# MCU176.net
KiCad netlist of a schematic drawn in Altium Designer
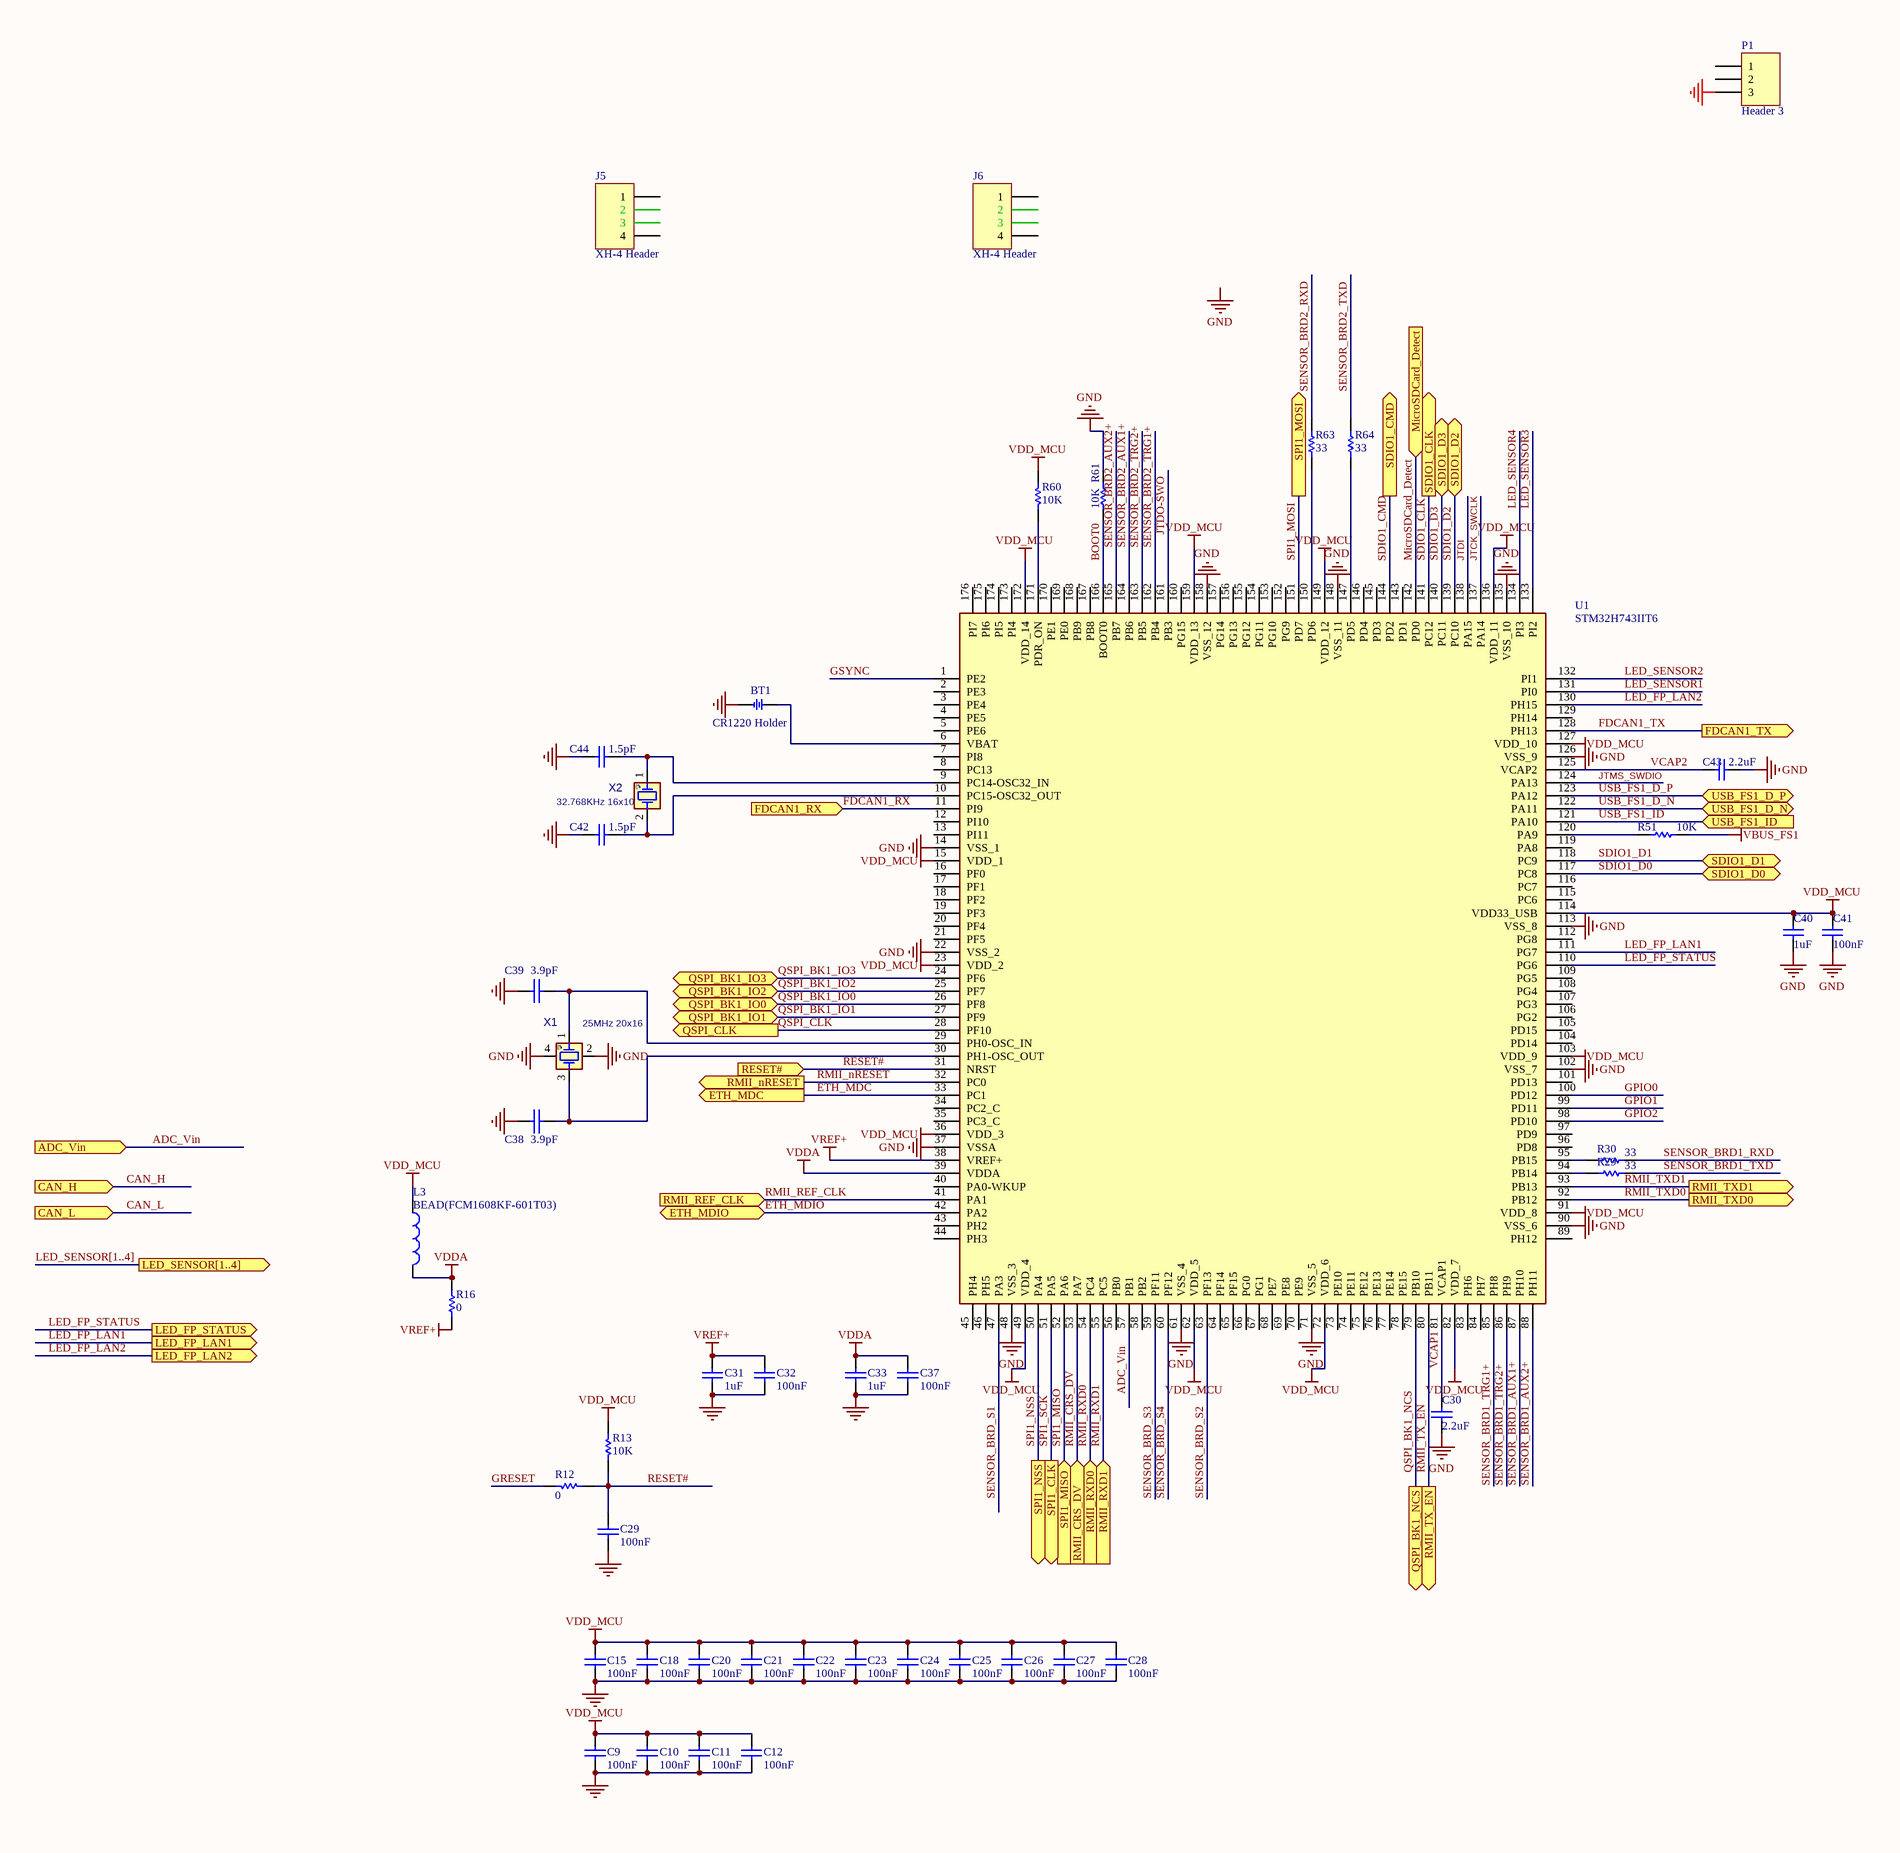
[diagram p0: MCU176.SchDoc, left]
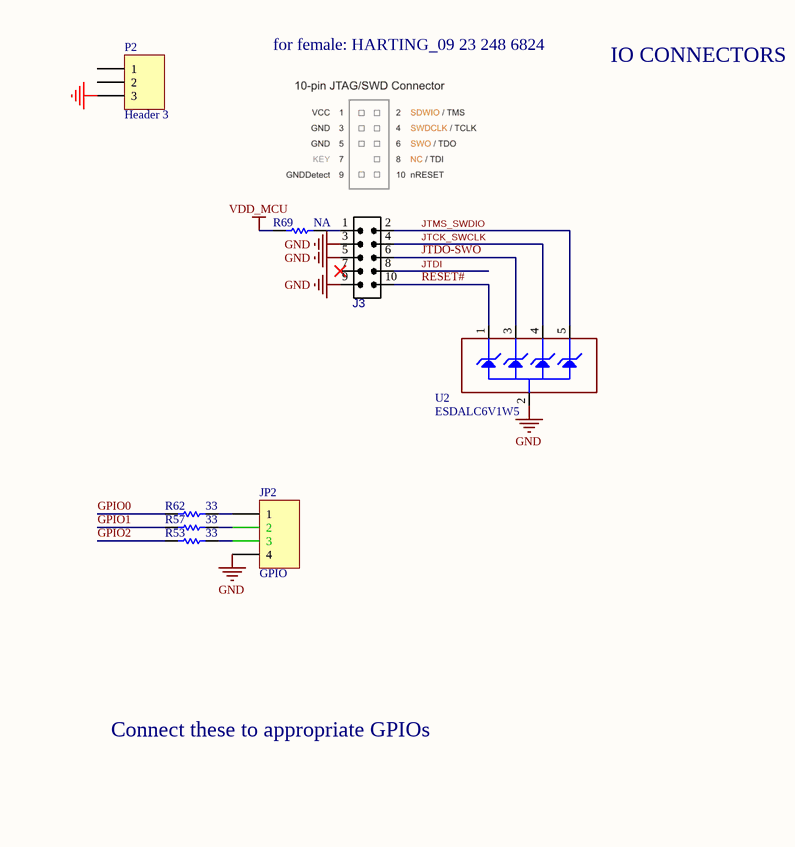
[diagram p1: MCU176.SchDoc, right]

(export (version "E")
  (design (tool "Eeschema 10.0.6"))
  (components
    (comp (ref "BT1")
      (value "CR1220 Holder")
      (footprint "BTH1220")
      (description "BATTERY HOLDER, CR1220")
      (libsource (lib "battery") (part "BATH_CR1220"))
    )
    (comp (ref "C9")
      (value "100nF")
      (footprint "C0603")
      (fields (field (name "PUBLISHER") "Altium Limited"))
      (libsource (lib "Miscellaneous Devices") (part "CAP"))
    )
    (comp (ref "C10")
      (value "100nF")
      (footprint "C0603")
      (fields (field (name "PUBLISHER") "Altium Limited"))
      (libsource (lib "Miscellaneous Devices") (part "CAP"))
    )
    (comp (ref "C11")
      (value "100nF")
      (footprint "C0603")
      (fields (field (name "PUBLISHER") "Altium Limited"))
      (libsource (lib "Miscellaneous Devices") (part "CAP"))
    )
    (comp (ref "C12")
      (value "100nF")
      (footprint "C0603")
      (fields (field (name "PUBLISHER") "Altium Limited"))
      (libsource (lib "Miscellaneous Devices") (part "CAP"))
    )
    (comp (ref "C15")
      (value "100nF")
      (footprint "C0603")
      (fields (field (name "PUBLISHER") "Altium Limited"))
      (libsource (lib "Miscellaneous Devices") (part "CAP"))
    )
    (comp (ref "C18")
      (value "100nF")
      (footprint "C0603")
      (fields (field (name "PUBLISHER") "Altium Limited"))
      (libsource (lib "Miscellaneous Devices") (part "CAP"))
    )
    (comp (ref "C20")
      (value "100nF")
      (footprint "C0603")
      (fields (field (name "PUBLISHER") "Altium Limited"))
      (libsource (lib "Miscellaneous Devices") (part "CAP"))
    )
    (comp (ref "C21")
      (value "100nF")
      (footprint "C0603")
      (fields (field (name "PUBLISHER") "Altium Limited"))
      (libsource (lib "Miscellaneous Devices") (part "CAP"))
    )
    (comp (ref "C22")
      (value "100nF")
      (footprint "C0603")
      (fields (field (name "PUBLISHER") "Altium Limited"))
      (libsource (lib "Miscellaneous Devices") (part "CAP"))
    )
    (comp (ref "C23")
      (value "100nF")
      (footprint "C0603")
      (fields (field (name "PUBLISHER") "Altium Limited"))
      (libsource (lib "Miscellaneous Devices") (part "CAP"))
    )
    (comp (ref "C24")
      (value "100nF")
      (footprint "C0603")
      (fields (field (name "PUBLISHER") "Altium Limited"))
      (libsource (lib "Miscellaneous Devices") (part "CAP"))
    )
    (comp (ref "C25")
      (value "100nF")
      (footprint "C0603")
      (fields (field (name "PUBLISHER") "Altium Limited"))
      (libsource (lib "Miscellaneous Devices") (part "CAP"))
    )
    (comp (ref "C26")
      (value "100nF")
      (footprint "C0603")
      (fields (field (name "PUBLISHER") "Altium Limited"))
      (libsource (lib "Miscellaneous Devices") (part "CAP"))
    )
    (comp (ref "C27")
      (value "100nF")
      (footprint "C0603")
      (fields (field (name "PUBLISHER") "Altium Limited"))
      (libsource (lib "Miscellaneous Devices") (part "CAP"))
    )
    (comp (ref "C28")
      (value "100nF")
      (footprint "C0603")
      (fields (field (name "PUBLISHER") "Altium Limited"))
      (libsource (lib "Miscellaneous Devices") (part "CAP"))
    )
    (comp (ref "C29")
      (value "100nF")
      (footprint "C0603")
      (fields (field (name "PUBLISHER") "Altium Limited"))
      (libsource (lib "Miscellaneous Devices") (part "CAP"))
    )
    (comp (ref "C30")
      (value "2.2uF")
      (footprint "C0603")
      (fields (field (name "PUBLISHER") "Altium Limited"))
      (libsource (lib "Miscellaneous Devices") (part "Cap"))
    )
    (comp (ref "C31")
      (value "1uF")
      (footprint "C0603")
      (fields (field (name "PUBLISHER") "Altium Limited"))
      (libsource (lib "Miscellaneous Devices") (part "Cap"))
    )
    (comp (ref "C32")
      (value "100nF")
      (footprint "C0603")
      (fields (field (name "PUBLISHER") "Altium Limited"))
      (libsource (lib "Miscellaneous Devices") (part "Cap"))
    )
    (comp (ref "C33")
      (value "1uF")
      (footprint "C0603")
      (fields (field (name "PUBLISHER") "Altium Limited"))
      (libsource (lib "Miscellaneous Devices") (part "Cap"))
    )
    (comp (ref "C37")
      (value "100nF")
      (footprint "C0603")
      (fields (field (name "PUBLISHER") "Altium Limited"))
      (libsource (lib "Miscellaneous Devices") (part "Cap"))
    )
    (comp (ref "C38") (value "3.9pF") (footprint "C0603") (libsource (lib "*") (part "CAP")))
    (comp (ref "C39") (value "3.9pF") (footprint "C0603") (libsource (lib "*") (part "CAP")))
    (comp (ref "C40")
      (value "1uF")
      (footprint "C0603")
      (fields (field (name "PUBLISHER") "Altium Limited"))
      (libsource (lib "Miscellaneous Devices") (part "Cap"))
    )
    (comp (ref "C41")
      (value "100nF")
      (footprint "C0603")
      (fields (field (name "PUBLISHER") "Altium Limited"))
      (libsource (lib "Miscellaneous Devices") (part "Cap"))
    )
    (comp (ref "C42") (value "1.5pF") (footprint "C0603") (libsource (lib "MCD_TOOLS") (part "Capacitor_ST")))
    (comp (ref "C43")
      (value "2.2uF")
      (footprint "C0603")
      (fields (field (name "PUBLISHER") "Altium Limited"))
      (libsource (lib "Miscellaneous Devices") (part "Cap"))
    )
    (comp (ref "C44") (value "1.5pF") (footprint "C0603") (libsource (lib "MCD_TOOLS") (part "Capacitor_ST")))
    (comp (ref "J3")
      (value "IDC_2X5")
      (footprint "IDC_2X5")
      (description "CONN, IDC, Male, pitch: 2.54mm, 10POS")
      (libsource (lib "conn_header_idc") (part "IDC_2X5"))
    )
    (comp (ref "J5")
      (value "XH-4 Header")
      (footprint "XH-4")
      (description "CONN HEADER 4POS 2.54MM VERT T/H MALE")
      (fields (field (name "MANUFACTURER") "TE Connectivity"))
      (libsource (lib "Miscellaneous Connectors") (part "Header 4"))
    )
    (comp (ref "J6")
      (value "XH-4 Header")
      (footprint "XH-4")
      (description "CONN HEADER 4POS 2.54MM VERT T/H MALE")
      (fields (field (name "MANUFACTURER") "TE Connectivity"))
      (libsource (lib "Miscellaneous Connectors") (part "Header 4"))
    )
    (comp (ref "JP2")
      (value "GPIO")
      (footprint "XH-4")
      (description "CONN HEADER 4POS 2.54MM VERT T/H MALE")
      (fields (field (name "MANUFACTURER") "TE Connectivity"))
      (libsource (lib "") (part "Header 4_1"))
    )
    (comp (ref "L3")
      (value "BEAD(FCM1608KF-601T03)")
      (footprint "L0603E")
      (description "Inductor")
      (fields (field (name "PUBLISHER") "Altium Limited"))
      (libsource (lib "Miscellaneous Devices") (part "Inductor"))
    )
    (comp (ref "P1")
      (value "Header 3")
      (footprint "xh-3")
      (description "Header, 3-Pin")
      (fields (field (name "PUBLISHER") "Altium Limited"))
      (libsource (lib "Miscellaneous Connectors") (part "Header 3"))
    )
    (comp (ref "P2")
      (value "Header 3")
      (footprint "xh-3")
      (description "Header, 3-Pin")
      (fields (field (name "PUBLISHER") "Altium Limited"))
      (libsource (lib "Miscellaneous Connectors") (part "Header 3"))
    )
    (comp (ref "R12")
      (value "0")
      (footprint "R0603")
      (fields (field (name "PUBLISHER") "Altium Limited"))
      (libsource (lib "Miscellaneous Devices") (part "Res1"))
    )
    (comp (ref "R13")
      (value "10K")
      (footprint "R0603")
      (fields (field (name "PUBLISHER") "Altium Limited"))
      (libsource (lib "Miscellaneous Devices") (part "Res1"))
    )
    (comp (ref "R16")
      (value "0")
      (footprint "R0603")
      (fields (field (name "PUBLISHER") "Altium Limited"))
      (libsource (lib "Miscellaneous Devices") (part "Res1"))
    )
    (comp (ref "R29")
      (value "33")
      (footprint "R0603")
      (fields (field (name "PUBLISHER") "Altium Limited"))
      (libsource (lib "Miscellaneous Devices") (part "Res1"))
    )
    (comp (ref "R30")
      (value "33")
      (footprint "R0603")
      (fields (field (name "PUBLISHER") "Altium Limited"))
      (libsource (lib "Miscellaneous Devices") (part "Res1"))
    )
    (comp (ref "R51")
      (value "10K")
      (footprint "R0603")
      (fields (field (name "PUBLISHER") "Altium Limited"))
      (libsource (lib "Miscellaneous Devices") (part "Res1"))
    )
    (comp (ref "R53")
      (value "33")
      (footprint "R0603")
      (fields (field (name "PUBLISHER") "Altium Limited"))
      (libsource (lib "Miscellaneous Devices") (part "Res1"))
    )
    (comp (ref "R57")
      (value "33")
      (footprint "R0603")
      (fields (field (name "PUBLISHER") "Altium Limited"))
      (libsource (lib "Miscellaneous Devices") (part "Res1"))
    )
    (comp (ref "R60")
      (value "10K")
      (footprint "R0603")
      (fields (field (name "PUBLISHER") "Altium Limited"))
      (libsource (lib "Miscellaneous Devices") (part "Res1"))
    )
    (comp (ref "R61")
      (value "10K")
      (footprint "R0603")
      (fields (field (name "PUBLISHER") "Altium Limited"))
      (libsource (lib "Miscellaneous Devices") (part "res1"))
    )
    (comp (ref "R62")
      (value "33")
      (footprint "R0603")
      (fields (field (name "PUBLISHER") "Altium Limited"))
      (libsource (lib "Miscellaneous Devices") (part "Res1"))
    )
    (comp (ref "R63")
      (value "33")
      (footprint "R0603")
      (fields (field (name "PUBLISHER") "Altium Limited"))
      (libsource (lib "Miscellaneous Devices") (part "Res1"))
    )
    (comp (ref "R64")
      (value "33")
      (footprint "R0603")
      (fields (field (name "PUBLISHER") "Altium Limited"))
      (libsource (lib "Miscellaneous Devices") (part "Res1"))
    )
    (comp (ref "R69")
      (value "NA")
      (footprint "R0603")
      (fields (field (name "PUBLISHER") "Altium Limited"))
      (libsource (lib "Miscellaneous Devices") (part "Res1"))
    )
    (comp (ref "U1")
      (value "STM32H743IIT6")
      (footprint "SamacSys:QFP50P2600X2600X160-176N")
      (description "Integrated Circuit")
      (fields (field (name "MOUSER PART NUMBER") "511-STM32H743IIT6"))
      (libsource (lib "*") (part "STM32H743IIT6"))
    )
    (comp (ref "U2")
      (value "ESDALC6V1W5")
      (footprint "samacsys:SOT65P210X110-5N")
      (description "Dual Transil array for ESD protection")
      (libsource (lib "MB1167_1") (part "ESDALC6V1W5"))
    )
    (comp (ref "X1")
      (value "25MHz 20x16")
      (footprint "XTL_4_2016")
      (description "CRYSTAL")
      (fields (field (name "MANF_P#") "XRCGB25M000F1H00R0"))
      (libsource (lib "crystal") (part "XTL_4_25MHz_3225"))
    )
    (comp (ref "X2")
      (value "32.768KHz 16x10")
      (footprint "XTL_2_1610")
      (description "Crystal")
      (fields (field (name "MANF_P#") "ABS05-32.768KHZ-9-T"))
      (libsource (lib "crystal") (part "XTL_2_32.768_3215A"))
    )
  )
  (nets
    (net (code "1") (name "/ADC_Vin") (class "Default")
      (node (ref "U1") (pin "57") (pinfunction "PB1_57") (pintype "passive"))
    )
    (net (code "2") (name "/BOOT0") (class "Default")
      (node (ref "R61") (pin "1") (pinfunction "1_1") (pintype "passive"))
      (node (ref "U1") (pin "166") (pinfunction "BOOT0_166") (pintype "passive"))
    )
    (net (code "5") (name "/ETH_MDC") (class "Default")
      (node (ref "U1") (pin "33") (pinfunction "PC1_33") (pintype "passive"))
    )
    (net (code "6") (name "/ETH_MDIO") (class "Default")
      (node (ref "U1") (pin "42") (pinfunction "PA2_42") (pintype "passive"))
    )
    (net (code "7") (name "/FDCAN1_RX") (class "Default")
      (node (ref "U1") (pin "11") (pinfunction "PI9_11") (pintype "passive"))
    )
    (net (code "8") (name "/FDCAN1_TX") (class "Default")
      (node (ref "U1") (pin "128") (pinfunction "PH13_128") (pintype "passive"))
    )
    (net (code "9") (name "/GPIO0") (class "Default")
      (node (ref "R62") (pin "2") (pinfunction "2_2") (pintype "passive"))
      (node (ref "U1") (pin "100") (pinfunction "PD12_100") (pintype "passive"))
    )
    (net (code "10") (name "/GPIO1") (class "Default")
      (node (ref "R57") (pin "2") (pinfunction "2_2") (pintype "passive"))
      (node (ref "U1") (pin "99") (pinfunction "PD11_99") (pintype "passive"))
    )
    (net (code "11") (name "/GPIO2") (class "Default")
      (node (ref "R53") (pin "2") (pinfunction "2_2") (pintype "passive"))
      (node (ref "U1") (pin "98") (pinfunction "PD10_98") (pintype "passive"))
    )
    (net (code "12") (name "/GRESET") (class "Default")
      (node (ref "R12") (pin "1") (pinfunction "1_1") (pintype "passive"))
    )
    (net (code "13") (name "/GSYNC") (class "Default")
      (node (ref "U1") (pin "1") (pinfunction "PE2_1") (pintype "passive"))
    )
    (net (code "14") (name "/JTCK_SWCLK") (class "Default")
      (node (ref "J3") (pin "4") (pinfunction "4_4") (pintype "passive"))
      (node (ref "U1") (pin "137") (pinfunction "PA14_137") (pintype "passive"))
      (node (ref "U2") (pin "4") (pinfunction "IO3_4") (pintype "passive"))
    )
    (net (code "15") (name "/JTDI") (class "Default")
      (node (ref "J3") (pin "8") (pinfunction "8_8") (pintype "passive"))
      (node (ref "U1") (pin "138") (pinfunction "PA15_138") (pintype "passive"))
    )
    (net (code "16") (name "/JTDO-SWO") (class "Default")
      (node (ref "J3") (pin "6") (pinfunction "6_6") (pintype "passive"))
      (node (ref "U1") (pin "161") (pinfunction "PB3_161") (pintype "passive"))
      (node (ref "U2") (pin "3") (pinfunction "IO2_3") (pintype "passive"))
    )
    (net (code "17") (name "/JTMS_SWDIO") (class "Default")
      (node (ref "J3") (pin "2") (pinfunction "2_2") (pintype "passive"))
      (node (ref "U1") (pin "124") (pinfunction "PA13_124") (pintype "passive"))
      (node (ref "U2") (pin "5") (pinfunction "IO4_5") (pintype "passive"))
    )
    (net (code "18") (name "/LED_FP_LAN1") (class "Default")
      (node (ref "U1") (pin "111") (pinfunction "PG7_111") (pintype "passive"))
    )
    (net (code "19") (name "/LED_FP_LAN2") (class "Default")
      (node (ref "U1") (pin "130") (pinfunction "PH15_130") (pintype "passive"))
    )
    (net (code "20") (name "/LED_FP_STATUS") (class "Default")
      (node (ref "U1") (pin "110") (pinfunction "PG6_110") (pintype "passive"))
    )
    (net (code "21") (name "/LED_SENSOR1") (class "Default")
      (node (ref "U1") (pin "131") (pinfunction "PI0_131") (pintype "passive"))
    )
    (net (code "22") (name "/LED_SENSOR2") (class "Default")
      (node (ref "U1") (pin "132") (pinfunction "PI1_132") (pintype "passive"))
    )
    (net (code "23") (name "/LED_SENSOR3") (class "Default")
      (node (ref "U1") (pin "133") (pinfunction "PI2_133") (pintype "passive"))
    )
    (net (code "24") (name "/LED_SENSOR4") (class "Default")
      (node (ref "U1") (pin "134") (pinfunction "PI3_134") (pintype "passive"))
    )
    (net (code "26") (name "/MicroSDCard_Detect") (class "Default")
      (node (ref "U1") (pin "142") (pinfunction "PD0_142") (pintype "passive"))
    )
    (net (code "27") (name "/QSPI_BK1_IO0") (class "Default")
      (node (ref "U1") (pin "26") (pinfunction "PF8_26") (pintype "passive"))
    )
    (net (code "28") (name "/QSPI_BK1_IO1") (class "Default")
      (node (ref "U1") (pin "27") (pinfunction "PF9_27") (pintype "passive"))
    )
    (net (code "29") (name "/QSPI_BK1_IO2") (class "Default")
      (node (ref "U1") (pin "25") (pinfunction "PF7_25") (pintype "passive"))
    )
    (net (code "30") (name "/QSPI_BK1_IO3") (class "Default")
      (node (ref "U1") (pin "24") (pinfunction "PF6_24") (pintype "passive"))
    )
    (net (code "31") (name "/QSPI_BK1_NCS") (class "Default")
      (node (ref "U1") (pin "79") (pinfunction "PB10_79") (pintype "passive"))
    )
    (net (code "32") (name "/QSPI_CLK") (class "Default")
      (node (ref "U1") (pin "28") (pinfunction "PF10_28") (pintype "passive"))
    )
    (net (code "33") (name "/RESET#") (class "Default")
      (node (ref "C29") (pin "2") (pinfunction "2_2") (pintype "passive"))
      (node (ref "J3") (pin "10") (pinfunction "10_10") (pintype "passive"))
      (node (ref "R12") (pin "2") (pinfunction "2_2") (pintype "passive"))
      (node (ref "R13") (pin "2") (pinfunction "2_2") (pintype "passive"))
      (node (ref "U1") (pin "31") (pinfunction "NRST_31") (pintype "passive"))
      (node (ref "U2") (pin "1") (pinfunction "IO1_1") (pintype "passive"))
    )
    (net (code "34") (name "/RMII_CRS_DV") (class "Default")
      (node (ref "U1") (pin "53") (pinfunction "PA7_53") (pintype "passive"))
    )
    (net (code "35") (name "/RMII_REF_CLK") (class "Default")
      (node (ref "U1") (pin "41") (pinfunction "PA1_41") (pintype "passive"))
    )
    (net (code "36") (name "/RMII_RXD0") (class "Default")
      (node (ref "U1") (pin "54") (pinfunction "PC4_54") (pintype "passive"))
    )
    (net (code "37") (name "/RMII_RXD1") (class "Default")
      (node (ref "U1") (pin "55") (pinfunction "PC5_55") (pintype "passive"))
    )
    (net (code "38") (name "/RMII_TXD0") (class "Default")
      (node (ref "U1") (pin "92") (pinfunction "PB12_92") (pintype "passive"))
    )
    (net (code "39") (name "/RMII_TXD1") (class "Default")
      (node (ref "U1") (pin "93") (pinfunction "PB13_93") (pintype "passive"))
    )
    (net (code "40") (name "/RMII_TX_EN") (class "Default")
      (node (ref "U1") (pin "80") (pinfunction "PB11_80") (pintype "passive"))
    )
    (net (code "41") (name "/RMII_nRESET") (class "Default")
      (node (ref "U1") (pin "32") (pinfunction "PC0_32") (pintype "passive"))
    )
    (net (code "42") (name "/SDIO1_CLK") (class "Default")
      (node (ref "U1") (pin "141") (pinfunction "PC12_141") (pintype "passive"))
    )
    (net (code "43") (name "/SDIO1_CMD") (class "Default")
      (node (ref "U1") (pin "144") (pinfunction "PD2_144") (pintype "passive"))
    )
    (net (code "44") (name "/SDIO1_D0") (class "Default")
      (node (ref "U1") (pin "117") (pinfunction "PC8_117") (pintype "passive"))
    )
    (net (code "45") (name "/SDIO1_D1") (class "Default")
      (node (ref "U1") (pin "118") (pinfunction "PC9_118") (pintype "passive"))
    )
    (net (code "46") (name "/SDIO1_D2") (class "Default")
      (node (ref "U1") (pin "139") (pinfunction "PC10_139") (pintype "passive"))
    )
    (net (code "47") (name "/SDIO1_D3") (class "Default")
      (node (ref "U1") (pin "140") (pinfunction "PC11_140") (pintype "passive"))
    )
    (net (code "48") (name "/SENSOR_BRD1_AUX1+") (class "Default")
      (node (ref "U1") (pin "87") (pinfunction "PH10_87") (pintype "passive"))
    )
    (net (code "49") (name "/SENSOR_BRD1_AUX2+") (class "Default")
      (node (ref "U1") (pin "88") (pinfunction "PH11_88") (pintype "passive"))
    )
    (net (code "50") (name "/SENSOR_BRD1_RXD") (class "Default")
      (node (ref "R30") (pin "2") (pinfunction "2_2") (pintype "passive"))
    )
    (net (code "51") (name "/SENSOR_BRD1_TRG1+") (class "Default")
      (node (ref "U1") (pin "85") (pinfunction "PH8_85") (pintype "passive"))
    )
    (net (code "52") (name "/SENSOR_BRD1_TRG2+") (class "Default")
      (node (ref "U1") (pin "86") (pinfunction "PH9_86") (pintype "passive"))
    )
    (net (code "53") (name "/SENSOR_BRD1_TXD") (class "Default")
      (node (ref "R29") (pin "2") (pinfunction "2_2") (pintype "passive"))
    )
    (net (code "54") (name "/SENSOR_BRD2_AUX1+") (class "Default")
      (node (ref "U1") (pin "164") (pinfunction "PB6_164") (pintype "passive"))
    )
    (net (code "55") (name "/SENSOR_BRD2_AUX2+") (class "Default")
      (node (ref "U1") (pin "165") (pinfunction "PB7_165") (pintype "passive"))
    )
    (net (code "56") (name "/SENSOR_BRD2_RXD") (class "Default")
      (node (ref "R63") (pin "1") (pinfunction "1_1") (pintype "passive"))
    )
    (net (code "57") (name "/SENSOR_BRD2_TRG1+") (class "Default")
      (node (ref "U1") (pin "162") (pinfunction "PB4_162") (pintype "passive"))
    )
    (net (code "58") (name "/SENSOR_BRD2_TRG2+") (class "Default")
      (node (ref "U1") (pin "163") (pinfunction "PB5_163") (pintype "passive"))
    )
    (net (code "59") (name "/SENSOR_BRD2_TXD") (class "Default")
      (node (ref "R64") (pin "1") (pinfunction "1_1") (pintype "passive"))
    )
    (net (code "60") (name "/SENSOR_BRD_S1") (class "Default")
      (node (ref "U1") (pin "47") (pinfunction "PA3_47") (pintype "passive"))
    )
    (net (code "61") (name "/SENSOR_BRD_S2") (class "Default")
      (node (ref "U1") (pin "63") (pinfunction "PF13_63") (pintype "passive"))
    )
    (net (code "62") (name "/SENSOR_BRD_S3") (class "Default")
      (node (ref "U1") (pin "59") (pinfunction "PF11_59") (pintype "passive"))
    )
    (net (code "63") (name "/SENSOR_BRD_S4") (class "Default")
      (node (ref "U1") (pin "60") (pinfunction "PF12_60") (pintype "passive"))
    )
    (net (code "64") (name "/SPI1_MISO") (class "Default")
      (node (ref "U1") (pin "52") (pinfunction "PA6_52") (pintype "passive"))
    )
    (net (code "65") (name "/SPI1_MOSI") (class "Default")
      (node (ref "U1") (pin "151") (pinfunction "PD7_151") (pintype "passive"))
    )
    (net (code "66") (name "/SPI1_NSS") (class "Default")
      (node (ref "U1") (pin "50") (pinfunction "PA4_50") (pintype "passive"))
    )
    (net (code "67") (name "/SPI1_SCK") (class "Default")
      (node (ref "U1") (pin "51") (pinfunction "PA5_51") (pintype "passive"))
    )
    (net (code "68") (name "/USB_FS1_D_N") (class "Default")
      (node (ref "U1") (pin "122") (pinfunction "PA11_122") (pintype "passive"))
    )
    (net (code "69") (name "/USB_FS1_D_P") (class "Default")
      (node (ref "U1") (pin "123") (pinfunction "PA12_123") (pintype "passive"))
    )
    (net (code "70") (name "/USB_FS1_ID") (class "Default")
      (node (ref "U1") (pin "121") (pinfunction "PA10_121") (pintype "passive"))
    )
    (net (code "71") (name "/VCAP1") (class "Default")
      (node (ref "C30") (pin "2") (pinfunction "2_2") (pintype "passive"))
      (node (ref "U1") (pin "81") (pinfunction "VCAP1_81") (pintype "power_in"))
    )
    (net (code "72") (name "/VCAP2") (class "Default")
      (node (ref "C43") (pin "1") (pinfunction "1_1") (pintype "passive"))
      (node (ref "U1") (pin "125") (pinfunction "VCAP2_125") (pintype "power_in"))
    )
    (net (code "73") (name "GND") (class "Default")
      (node (ref "BT1") (pin "2") (pinfunction "2_2") (pintype "passive"))
      (node (ref "C10") (pin "2") (pinfunction "2_2") (pintype "passive"))
      (node (ref "C11") (pin "2") (pinfunction "2_2") (pintype "passive"))
      (node (ref "C12") (pin "2") (pinfunction "2_2") (pintype "passive"))
      (node (ref "C15") (pin "2") (pinfunction "2_2") (pintype "passive"))
      (node (ref "C18") (pin "2") (pinfunction "2_2") (pintype "passive"))
      (node (ref "C20") (pin "2") (pinfunction "2_2") (pintype "passive"))
      (node (ref "C21") (pin "2") (pinfunction "2_2") (pintype "passive"))
      (node (ref "C22") (pin "2") (pinfunction "2_2") (pintype "passive"))
      (node (ref "C23") (pin "2") (pinfunction "2_2") (pintype "passive"))
      (node (ref "C24") (pin "2") (pinfunction "2_2") (pintype "passive"))
      (node (ref "C25") (pin "2") (pinfunction "2_2") (pintype "passive"))
      (node (ref "C26") (pin "2") (pinfunction "2_2") (pintype "passive"))
      (node (ref "C27") (pin "2") (pinfunction "2_2") (pintype "passive"))
      (node (ref "C28") (pin "2") (pinfunction "2_2") (pintype "passive"))
      (node (ref "C29") (pin "1") (pinfunction "1_1") (pintype "passive"))
      (node (ref "C30") (pin "1") (pinfunction "1_1") (pintype "passive"))
      (node (ref "C31") (pin "1") (pinfunction "1_1") (pintype "passive"))
      (node (ref "C32") (pin "1") (pinfunction "1_1") (pintype "passive"))
      (node (ref "C33") (pin "1") (pinfunction "1_1") (pintype "passive"))
      (node (ref "C37") (pin "1") (pinfunction "1_1") (pintype "passive"))
      (node (ref "C38") (pin "2") (pinfunction "2_2") (pintype "passive"))
      (node (ref "C39") (pin "2") (pinfunction "2_2") (pintype "passive"))
      (node (ref "C40") (pin "1") (pinfunction "1_1") (pintype "passive"))
      (node (ref "C41") (pin "1") (pinfunction "1_1") (pintype "passive"))
      (node (ref "C42") (pin "2") (pinfunction "2_2") (pintype "passive"))
      (node (ref "C43") (pin "2") (pinfunction "2_2") (pintype "passive"))
      (node (ref "C44") (pin "2") (pinfunction "2_2") (pintype "passive"))
      (node (ref "C9") (pin "2") (pinfunction "2_2") (pintype "passive"))
      (node (ref "J3") (pin "3") (pinfunction "3_3") (pintype "passive"))
      (node (ref "J3") (pin "5") (pinfunction "5_5") (pintype "passive"))
      (node (ref "J3") (pin "9") (pinfunction "9_9") (pintype "passive"))
      (node (ref "JP2") (pin "4") (pinfunction "4_4") (pintype "passive"))
      (node (ref "P1") (pin "3") (pinfunction "3_3") (pintype "passive"))
      (node (ref "P2") (pin "3") (pinfunction "3_3") (pintype "passive"))
      (node (ref "R61") (pin "2") (pinfunction "2_2") (pintype "passive"))
      (node (ref "U1") (pin "102") (pinfunction "VSS_7_102") (pintype "power_in"))
      (node (ref "U1") (pin "113") (pinfunction "VSS_8_113") (pintype "power_in"))
      (node (ref "U1") (pin "126") (pinfunction "VSS_9_126") (pintype "power_in"))
      (node (ref "U1") (pin "135") (pinfunction "VSS_10_135") (pintype "power_in"))
      (node (ref "U1") (pin "14") (pinfunction "VSS_1_14") (pintype "power_in"))
      (node (ref "U1") (pin "148") (pinfunction "VSS_11_148") (pintype "power_in"))
      (node (ref "U1") (pin "158") (pinfunction "VSS_12_158") (pintype "power_in"))
      (node (ref "U1") (pin "22") (pinfunction "VSS_2_22") (pintype "power_in"))
      (node (ref "U1") (pin "37") (pinfunction "VSSA_37") (pintype "power_in"))
      (node (ref "U1") (pin "48") (pinfunction "VSS_3_48") (pintype "power_in"))
      (node (ref "U1") (pin "61") (pinfunction "VSS_4_61") (pintype "power_in"))
      (node (ref "U1") (pin "71") (pinfunction "VSS_5_71") (pintype "power_in"))
      (node (ref "U1") (pin "90") (pinfunction "VSS_6_90") (pintype "power_in"))
      (node (ref "U2") (pin "2") (pinfunction "GND_2") (pintype "passive"))
      (node (ref "X1") (pin "2") (pinfunction "GND1_2") (pintype "passive"))
      (node (ref "X1") (pin "4") (pinfunction "GND2_4") (pintype "passive"))
    )
    (net (code "74") (name "Net-(J3-Pad1)") (class "Default")
      (node (ref "J3") (pin "1") (pinfunction "1_1") (pintype "passive"))
      (node (ref "R69") (pin "1") (pinfunction "1_1") (pintype "passive"))
    )
    (net (code "75") (name "Net-(JP2-Pad1)") (class "Default")
      (node (ref "JP2") (pin "1") (pinfunction "1_1") (pintype "passive"))
      (node (ref "R62") (pin "1") (pinfunction "1_1") (pintype "passive"))
    )
    (net (code "76") (name "Net-(JP2-Pad2)") (class "Default")
      (node (ref "JP2") (pin "2") (pinfunction "2_2") (pintype "passive"))
      (node (ref "R57") (pin "1") (pinfunction "1_1") (pintype "passive"))
    )
    (net (code "77") (name "Net-(JP2-Pad3)") (class "Default")
      (node (ref "JP2") (pin "3") (pinfunction "3_3") (pintype "passive"))
      (node (ref "R53") (pin "1") (pinfunction "1_1") (pintype "passive"))
    )
    (net (code "78") (name "Net-(U1-PA9)") (class "Default")
      (node (ref "R51") (pin "2") (pinfunction "2_2") (pintype "passive"))
      (node (ref "U1") (pin "120") (pinfunction "PA9_120") (pintype "passive"))
    )
    (net (code "79") (name "Net-(U1-PB14)") (class "Default")
      (node (ref "R29") (pin "1") (pinfunction "1_1") (pintype "passive"))
      (node (ref "U1") (pin "94") (pinfunction "PB14_94") (pintype "passive"))
    )
    (net (code "80") (name "Net-(U1-PB15)") (class "Default")
      (node (ref "R30") (pin "1") (pinfunction "1_1") (pintype "passive"))
      (node (ref "U1") (pin "95") (pinfunction "PB15_95") (pintype "passive"))
    )
    (net (code "81") (name "Net-(U1-PC14-OSC32_IN)") (class "Default")
      (node (ref "C44") (pin "1") (pinfunction "1_1") (pintype "passive"))
      (node (ref "U1") (pin "9") (pinfunction "PC14-OSC32_IN_9") (pintype "passive"))
      (node (ref "X2") (pin "1") (pinfunction "OSC1_1") (pintype "passive"))
    )
    (net (code "82") (name "Net-(U1-PC15-OSC32_OUT)") (class "Default")
      (node (ref "C42") (pin "1") (pinfunction "1_1") (pintype "passive"))
      (node (ref "U1") (pin "10") (pinfunction "PC15-OSC32_OUT_10") (pintype "passive"))
      (node (ref "X2") (pin "2") (pinfunction "OSC2_2") (pintype "passive"))
    )
    (net (code "83") (name "Net-(U1-PD5)") (class "Default")
      (node (ref "R64") (pin "2") (pinfunction "2_2") (pintype "passive"))
      (node (ref "U1") (pin "147") (pinfunction "PD5_147") (pintype "passive"))
    )
    (net (code "84") (name "Net-(U1-PD6)") (class "Default")
      (node (ref "R63") (pin "2") (pinfunction "2_2") (pintype "passive"))
      (node (ref "U1") (pin "150") (pinfunction "PD6_150") (pintype "passive"))
    )
    (net (code "85") (name "Net-(U1-PDR_ON)") (class "Default")
      (node (ref "R60") (pin "2") (pinfunction "2_2") (pintype "passive"))
      (node (ref "U1") (pin "171") (pinfunction "PDR_ON_171") (pintype "passive"))
    )
    (net (code "86") (name "Net-(U1-PH0-OSC_IN)") (class "Default")
      (node (ref "C39") (pin "1") (pinfunction "1_1") (pintype "passive"))
      (node (ref "U1") (pin "29") (pinfunction "PH0-OSC_IN_29") (pintype "passive"))
      (node (ref "X1") (pin "1") (pinfunction "XA_1") (pintype "passive"))
    )
    (net (code "87") (name "Net-(U1-PH1-OSC_OUT)") (class "Default")
      (node (ref "C38") (pin "1") (pinfunction "1_1") (pintype "passive"))
      (node (ref "U1") (pin "30") (pinfunction "PH1-OSC_OUT_30") (pintype "passive"))
      (node (ref "X1") (pin "3") (pinfunction "XB_3") (pintype "passive"))
    )
    (net (code "88") (name "Net-(U1-VBAT)") (class "Default")
      (node (ref "BT1") (pin "1") (pinfunction "1_1") (pintype "passive"))
      (node (ref "U1") (pin "6") (pinfunction "VBAT_6") (pintype "power_in"))
    )
    (net (code "89") (name "VBUS_FS1") (class "Default")
      (node (ref "R51") (pin "1") (pinfunction "1_1") (pintype "passive"))
    )
    (net (code "90") (name "VDDA") (class "Default")
      (node (ref "C33") (pin "2") (pinfunction "2_2") (pintype "passive"))
      (node (ref "C37") (pin "2") (pinfunction "2_2") (pintype "passive"))
      (node (ref "L3") (pin "2") (pinfunction "2_2") (pintype "passive"))
      (node (ref "R16") (pin "1") (pinfunction "1_1") (pintype "passive"))
      (node (ref "U1") (pin "39") (pinfunction "VDDA_39") (pintype "power_in"))
    )
    (net (code "91") (name "VDD_MCU") (class "Default")
      (node (ref "C10") (pin "1") (pinfunction "1_1") (pintype "passive"))
      (node (ref "C11") (pin "1") (pinfunction "1_1") (pintype "passive"))
      (node (ref "C12") (pin "1") (pinfunction "1_1") (pintype "passive"))
      (node (ref "C15") (pin "1") (pinfunction "1_1") (pintype "passive"))
      (node (ref "C18") (pin "1") (pinfunction "1_1") (pintype "passive"))
      (node (ref "C20") (pin "1") (pinfunction "1_1") (pintype "passive"))
      (node (ref "C21") (pin "1") (pinfunction "1_1") (pintype "passive"))
      (node (ref "C22") (pin "1") (pinfunction "1_1") (pintype "passive"))
      (node (ref "C23") (pin "1") (pinfunction "1_1") (pintype "passive"))
      (node (ref "C24") (pin "1") (pinfunction "1_1") (pintype "passive"))
      (node (ref "C25") (pin "1") (pinfunction "1_1") (pintype "passive"))
      (node (ref "C26") (pin "1") (pinfunction "1_1") (pintype "passive"))
      (node (ref "C27") (pin "1") (pinfunction "1_1") (pintype "passive"))
      (node (ref "C28") (pin "1") (pinfunction "1_1") (pintype "passive"))
      (node (ref "C40") (pin "2") (pinfunction "2_2") (pintype "passive"))
      (node (ref "C41") (pin "2") (pinfunction "2_2") (pintype "passive"))
      (node (ref "C9") (pin "1") (pinfunction "1_1") (pintype "passive"))
      (node (ref "L3") (pin "1") (pinfunction "1_1") (pintype "passive"))
      (node (ref "R13") (pin "1") (pinfunction "1_1") (pintype "passive"))
      (node (ref "R60") (pin "1") (pinfunction "1_1") (pintype "passive"))
      (node (ref "R69") (pin "2") (pinfunction "2_2") (pintype "passive"))
      (node (ref "U1") (pin "103") (pinfunction "VDD_9_103") (pintype "power_in"))
      (node (ref "U1") (pin "114") (pinfunction "VDD33_USB_114") (pintype "power_in"))
      (node (ref "U1") (pin "127") (pinfunction "VDD_10_127") (pintype "power_in"))
      (node (ref "U1") (pin "136") (pinfunction "VDD_11_136") (pintype "power_in"))
      (node (ref "U1") (pin "149") (pinfunction "VDD_12_149") (pintype "power_in"))
      (node (ref "U1") (pin "15") (pinfunction "VDD_1_15") (pintype "power_in"))
      (node (ref "U1") (pin "159") (pinfunction "VDD_13_159") (pintype "power_in"))
      (node (ref "U1") (pin "172") (pinfunction "VDD_14_172") (pintype "power_in"))
      (node (ref "U1") (pin "23") (pinfunction "VDD_2_23") (pintype "power_in"))
      (node (ref "U1") (pin "36") (pinfunction "VDD_3_36") (pintype "power_in"))
      (node (ref "U1") (pin "49") (pinfunction "VDD_4_49") (pintype "power_in"))
      (node (ref "U1") (pin "62") (pinfunction "VDD_5_62") (pintype "power_in"))
      (node (ref "U1") (pin "72") (pinfunction "VDD_6_72") (pintype "power_in"))
      (node (ref "U1") (pin "82") (pinfunction "VDD_7_82") (pintype "power_in"))
      (node (ref "U1") (pin "91") (pinfunction "VDD_8_91") (pintype "power_in"))
    )
    (net (code "92") (name "VREF+") (class "Default")
      (node (ref "C31") (pin "2") (pinfunction "2_2") (pintype "passive"))
      (node (ref "C32") (pin "2") (pinfunction "2_2") (pintype "passive"))
      (node (ref "R16") (pin "2") (pinfunction "2_2") (pintype "passive"))
      (node (ref "U1") (pin "38") (pinfunction "VREF+_38") (pintype "passive"))
    )
    (net (code "93") (name "unconnected-(J3-Pad7)") (class "Default")
      (node (ref "J3") (pin "7") (pinfunction "7_7") (pintype "passive+no_connect"))
    )
    (net (code "94") (name "unconnected-(J5-Pad1)") (class "Default")
      (node (ref "J5") (pin "1") (pinfunction "1_1") (pintype "passive"))
    )
    (net (code "95") (name "unconnected-(J5-Pad2)") (class "Default")
      (node (ref "J5") (pin "2") (pinfunction "2_2") (pintype "passive"))
    )
    (net (code "96") (name "unconnected-(J5-Pad3)") (class "Default")
      (node (ref "J5") (pin "3") (pinfunction "3_3") (pintype "passive"))
    )
    (net (code "97") (name "unconnected-(J5-Pad4)") (class "Default")
      (node (ref "J5") (pin "4") (pinfunction "4_4") (pintype "passive"))
    )
    (net (code "98") (name "unconnected-(J6-Pad1)") (class "Default")
      (node (ref "J6") (pin "1") (pinfunction "1_1") (pintype "passive"))
    )
    (net (code "99") (name "unconnected-(J6-Pad2)") (class "Default")
      (node (ref "J6") (pin "2") (pinfunction "2_2") (pintype "passive"))
    )
    (net (code "100") (name "unconnected-(J6-Pad3)") (class "Default")
      (node (ref "J6") (pin "3") (pinfunction "3_3") (pintype "passive"))
    )
    (net (code "101") (name "unconnected-(J6-Pad4)") (class "Default")
      (node (ref "J6") (pin "4") (pinfunction "4_4") (pintype "passive"))
    )
    (net (code "102") (name "unconnected-(P1-Pad1)") (class "Default")
      (node (ref "P1") (pin "1") (pinfunction "1_1") (pintype "passive"))
    )
    (net (code "103") (name "unconnected-(P1-Pad2)") (class "Default")
      (node (ref "P1") (pin "2") (pinfunction "2_2") (pintype "passive"))
    )
    (net (code "104") (name "unconnected-(P2-Pad1)") (class "Default")
      (node (ref "P2") (pin "1") (pinfunction "1_1") (pintype "passive"))
    )
    (net (code "105") (name "unconnected-(P2-Pad2)") (class "Default")
      (node (ref "P2") (pin "2") (pinfunction "2_2") (pintype "passive"))
    )
    (net (code "106") (name "unconnected-(U1-PA0-WKUP-Pad40)") (class "Default")
      (node (ref "U1") (pin "40") (pinfunction "PA0-WKUP_40") (pintype "passive"))
    )
    (net (code "107") (name "unconnected-(U1-PA8-Pad119)") (class "Default")
      (node (ref "U1") (pin "119") (pinfunction "PA8_119") (pintype "passive"))
    )
    (net (code "108") (name "unconnected-(U1-PB0-Pad56)") (class "Default")
      (node (ref "U1") (pin "56") (pinfunction "PB0_56") (pintype "passive"))
    )
    (net (code "109") (name "unconnected-(U1-PB2-Pad58)") (class "Default")
      (node (ref "U1") (pin "58") (pinfunction "PB2_58") (pintype "passive"))
    )
    (net (code "110") (name "unconnected-(U1-PB8-Pad167)") (class "Default")
      (node (ref "U1") (pin "167") (pinfunction "PB8_167") (pintype "passive"))
    )
    (net (code "111") (name "unconnected-(U1-PB9-Pad168)") (class "Default")
      (node (ref "U1") (pin "168") (pinfunction "PB9_168") (pintype "passive"))
    )
    (net (code "112") (name "unconnected-(U1-PC2_C-Pad34)") (class "Default")
      (node (ref "U1") (pin "34") (pinfunction "PC2_C_34") (pintype "passive"))
    )
    (net (code "113") (name "unconnected-(U1-PC3_C-Pad35)") (class "Default")
      (node (ref "U1") (pin "35") (pinfunction "PC3_C_35") (pintype "passive"))
    )
    (net (code "114") (name "unconnected-(U1-PC6-Pad115)") (class "Default")
      (node (ref "U1") (pin "115") (pinfunction "PC6_115") (pintype "passive"))
    )
    (net (code "115") (name "unconnected-(U1-PC7-Pad116)") (class "Default")
      (node (ref "U1") (pin "116") (pinfunction "PC7_116") (pintype "passive"))
    )
    (net (code "116") (name "unconnected-(U1-PC13-Pad8)") (class "Default")
      (node (ref "U1") (pin "8") (pinfunction "PC13_8") (pintype "passive"))
    )
    (net (code "117") (name "unconnected-(U1-PD1-Pad143)") (class "Default")
      (node (ref "U1") (pin "143") (pinfunction "PD1_143") (pintype "passive"))
    )
    (net (code "118") (name "unconnected-(U1-PD3-Pad145)") (class "Default")
      (node (ref "U1") (pin "145") (pinfunction "PD3_145") (pintype "passive"))
    )
    (net (code "119") (name "unconnected-(U1-PD4-Pad146)") (class "Default")
      (node (ref "U1") (pin "146") (pinfunction "PD4_146") (pintype "passive"))
    )
    (net (code "120") (name "unconnected-(U1-PD8-Pad96)") (class "Default")
      (node (ref "U1") (pin "96") (pinfunction "PD8_96") (pintype "passive"))
    )
    (net (code "121") (name "unconnected-(U1-PD9-Pad97)") (class "Default")
      (node (ref "U1") (pin "97") (pinfunction "PD9_97") (pintype "passive"))
    )
    (net (code "122") (name "unconnected-(U1-PD13-Pad101)") (class "Default")
      (node (ref "U1") (pin "101") (pinfunction "PD13_101") (pintype "passive"))
    )
    (net (code "123") (name "unconnected-(U1-PD14-Pad104)") (class "Default")
      (node (ref "U1") (pin "104") (pinfunction "PD14_104") (pintype "passive"))
    )
    (net (code "124") (name "unconnected-(U1-PD15-Pad105)") (class "Default")
      (node (ref "U1") (pin "105") (pinfunction "PD15_105") (pintype "passive"))
    )
    (net (code "125") (name "unconnected-(U1-PE0-Pad169)") (class "Default")
      (node (ref "U1") (pin "169") (pinfunction "PE0_169") (pintype "passive"))
    )
    (net (code "126") (name "unconnected-(U1-PE1-Pad170)") (class "Default")
      (node (ref "U1") (pin "170") (pinfunction "PE1_170") (pintype "passive"))
    )
    (net (code "127") (name "unconnected-(U1-PE3-Pad2)") (class "Default")
      (node (ref "U1") (pin "2") (pinfunction "PE3_2") (pintype "passive"))
    )
    (net (code "128") (name "unconnected-(U1-PE4-Pad3)") (class "Default")
      (node (ref "U1") (pin "3") (pinfunction "PE4_3") (pintype "passive"))
    )
    (net (code "129") (name "unconnected-(U1-PE5-Pad4)") (class "Default")
      (node (ref "U1") (pin "4") (pinfunction "PE5_4") (pintype "passive"))
    )
    (net (code "130") (name "unconnected-(U1-PE6-Pad5)") (class "Default")
      (node (ref "U1") (pin "5") (pinfunction "PE6_5") (pintype "passive"))
    )
    (net (code "131") (name "unconnected-(U1-PE7-Pad68)") (class "Default")
      (node (ref "U1") (pin "68") (pinfunction "PE7_68") (pintype "passive"))
    )
    (net (code "132") (name "unconnected-(U1-PE8-Pad69)") (class "Default")
      (node (ref "U1") (pin "69") (pinfunction "PE8_69") (pintype "passive"))
    )
    (net (code "133") (name "unconnected-(U1-PE9-Pad70)") (class "Default")
      (node (ref "U1") (pin "70") (pinfunction "PE9_70") (pintype "passive"))
    )
    (net (code "134") (name "unconnected-(U1-PE10-Pad73)") (class "Default")
      (node (ref "U1") (pin "73") (pinfunction "PE10_73") (pintype "passive"))
    )
    (net (code "135") (name "unconnected-(U1-PE11-Pad74)") (class "Default")
      (node (ref "U1") (pin "74") (pinfunction "PE11_74") (pintype "passive"))
    )
    (net (code "136") (name "unconnected-(U1-PE12-Pad75)") (class "Default")
      (node (ref "U1") (pin "75") (pinfunction "PE12_75") (pintype "passive"))
    )
    (net (code "137") (name "unconnected-(U1-PE13-Pad76)") (class "Default")
      (node (ref "U1") (pin "76") (pinfunction "PE13_76") (pintype "passive"))
    )
    (net (code "138") (name "unconnected-(U1-PE14-Pad77)") (class "Default")
      (node (ref "U1") (pin "77") (pinfunction "PE14_77") (pintype "passive"))
    )
    (net (code "139") (name "unconnected-(U1-PE15-Pad78)") (class "Default")
      (node (ref "U1") (pin "78") (pinfunction "PE15_78") (pintype "passive"))
    )
    (net (code "140") (name "unconnected-(U1-PF0-Pad16)") (class "Default")
      (node (ref "U1") (pin "16") (pinfunction "PF0_16") (pintype "passive"))
    )
    (net (code "141") (name "unconnected-(U1-PF1-Pad17)") (class "Default")
      (node (ref "U1") (pin "17") (pinfunction "PF1_17") (pintype "passive"))
    )
    (net (code "142") (name "unconnected-(U1-PF2-Pad18)") (class "Default")
      (node (ref "U1") (pin "18") (pinfunction "PF2_18") (pintype "passive"))
    )
    (net (code "143") (name "unconnected-(U1-PF3-Pad19)") (class "Default")
      (node (ref "U1") (pin "19") (pinfunction "PF3_19") (pintype "passive"))
    )
    (net (code "144") (name "unconnected-(U1-PF4-Pad20)") (class "Default")
      (node (ref "U1") (pin "20") (pinfunction "PF4_20") (pintype "passive"))
    )
    (net (code "145") (name "unconnected-(U1-PF5-Pad21)") (class "Default")
      (node (ref "U1") (pin "21") (pinfunction "PF5_21") (pintype "passive"))
    )
    (net (code "146") (name "unconnected-(U1-PF14-Pad64)") (class "Default")
      (node (ref "U1") (pin "64") (pinfunction "PF14_64") (pintype "passive"))
    )
    (net (code "147") (name "unconnected-(U1-PF15-Pad65)") (class "Default")
      (node (ref "U1") (pin "65") (pinfunction "PF15_65") (pintype "passive"))
    )
    (net (code "148") (name "unconnected-(U1-PG0-Pad66)") (class "Default")
      (node (ref "U1") (pin "66") (pinfunction "PG0_66") (pintype "passive"))
    )
    (net (code "149") (name "unconnected-(U1-PG1-Pad67)") (class "Default")
      (node (ref "U1") (pin "67") (pinfunction "PG1_67") (pintype "passive"))
    )
    (net (code "150") (name "unconnected-(U1-PG2-Pad106)") (class "Default")
      (node (ref "U1") (pin "106") (pinfunction "PG2_106") (pintype "passive"))
    )
    (net (code "151") (name "unconnected-(U1-PG3-Pad107)") (class "Default")
      (node (ref "U1") (pin "107") (pinfunction "PG3_107") (pintype "passive"))
    )
    (net (code "152") (name "unconnected-(U1-PG4-Pad108)") (class "Default")
      (node (ref "U1") (pin "108") (pinfunction "PG4_108") (pintype "passive"))
    )
    (net (code "153") (name "unconnected-(U1-PG5-Pad109)") (class "Default")
      (node (ref "U1") (pin "109") (pinfunction "PG5_109") (pintype "passive"))
    )
    (net (code "154") (name "unconnected-(U1-PG8-Pad112)") (class "Default")
      (node (ref "U1") (pin "112") (pinfunction "PG8_112") (pintype "passive"))
    )
    (net (code "155") (name "unconnected-(U1-PG9-Pad152)") (class "Default")
      (node (ref "U1") (pin "152") (pinfunction "PG9_152") (pintype "passive"))
    )
    (net (code "156") (name "unconnected-(U1-PG10-Pad153)") (class "Default")
      (node (ref "U1") (pin "153") (pinfunction "PG10_153") (pintype "passive"))
    )
    (net (code "157") (name "unconnected-(U1-PG11-Pad154)") (class "Default")
      (node (ref "U1") (pin "154") (pinfunction "PG11_154") (pintype "passive"))
    )
    (net (code "158") (name "unconnected-(U1-PG12-Pad155)") (class "Default")
      (node (ref "U1") (pin "155") (pinfunction "PG12_155") (pintype "passive"))
    )
    (net (code "159") (name "unconnected-(U1-PG13-Pad156)") (class "Default")
      (node (ref "U1") (pin "156") (pinfunction "PG13_156") (pintype "passive"))
    )
    (net (code "160") (name "unconnected-(U1-PG14-Pad157)") (class "Default")
      (node (ref "U1") (pin "157") (pinfunction "PG14_157") (pintype "passive"))
    )
    (net (code "161") (name "unconnected-(U1-PG15-Pad160)") (class "Default")
      (node (ref "U1") (pin "160") (pinfunction "PG15_160") (pintype "passive"))
    )
    (net (code "162") (name "unconnected-(U1-PH2-Pad43)") (class "Default")
      (node (ref "U1") (pin "43") (pinfunction "PH2_43") (pintype "passive"))
    )
    (net (code "163") (name "unconnected-(U1-PH3-Pad44)") (class "Default")
      (node (ref "U1") (pin "44") (pinfunction "PH3_44") (pintype "passive"))
    )
    (net (code "164") (name "unconnected-(U1-PH4-Pad45)") (class "Default")
      (node (ref "U1") (pin "45") (pinfunction "PH4_45") (pintype "passive"))
    )
    (net (code "165") (name "unconnected-(U1-PH5-Pad46)") (class "Default")
      (node (ref "U1") (pin "46") (pinfunction "PH5_46") (pintype "passive"))
    )
    (net (code "166") (name "unconnected-(U1-PH6-Pad83)") (class "Default")
      (node (ref "U1") (pin "83") (pinfunction "PH6_83") (pintype "passive"))
    )
    (net (code "167") (name "unconnected-(U1-PH7-Pad84)") (class "Default")
      (node (ref "U1") (pin "84") (pinfunction "PH7_84") (pintype "passive"))
    )
    (net (code "168") (name "unconnected-(U1-PH12-Pad89)") (class "Default")
      (node (ref "U1") (pin "89") (pinfunction "PH12_89") (pintype "passive"))
    )
    (net (code "169") (name "unconnected-(U1-PH14-Pad129)") (class "Default")
      (node (ref "U1") (pin "129") (pinfunction "PH14_129") (pintype "passive"))
    )
    (net (code "170") (name "unconnected-(U1-PI4-Pad173)") (class "Default")
      (node (ref "U1") (pin "173") (pinfunction "PI4_173") (pintype "passive"))
    )
    (net (code "171") (name "unconnected-(U1-PI5-Pad174)") (class "Default")
      (node (ref "U1") (pin "174") (pinfunction "PI5_174") (pintype "passive"))
    )
    (net (code "172") (name "unconnected-(U1-PI6-Pad175)") (class "Default")
      (node (ref "U1") (pin "175") (pinfunction "PI6_175") (pintype "passive"))
    )
    (net (code "173") (name "unconnected-(U1-PI7-Pad176)") (class "Default")
      (node (ref "U1") (pin "176") (pinfunction "PI7_176") (pintype "passive"))
    )
    (net (code "174") (name "unconnected-(U1-PI8-Pad7)") (class "Default")
      (node (ref "U1") (pin "7") (pinfunction "PI8_7") (pintype "passive"))
    )
    (net (code "175") (name "unconnected-(U1-PI10-Pad12)") (class "Default")
      (node (ref "U1") (pin "12") (pinfunction "PI10_12") (pintype "passive"))
    )
    (net (code "176") (name "unconnected-(U1-PI11-Pad13)") (class "Default")
      (node (ref "U1") (pin "13") (pinfunction "PI11_13") (pintype "passive"))
    )
  )
)
